# SD_card.net
KiCad netlist of a schematic drawn in Altium Designer
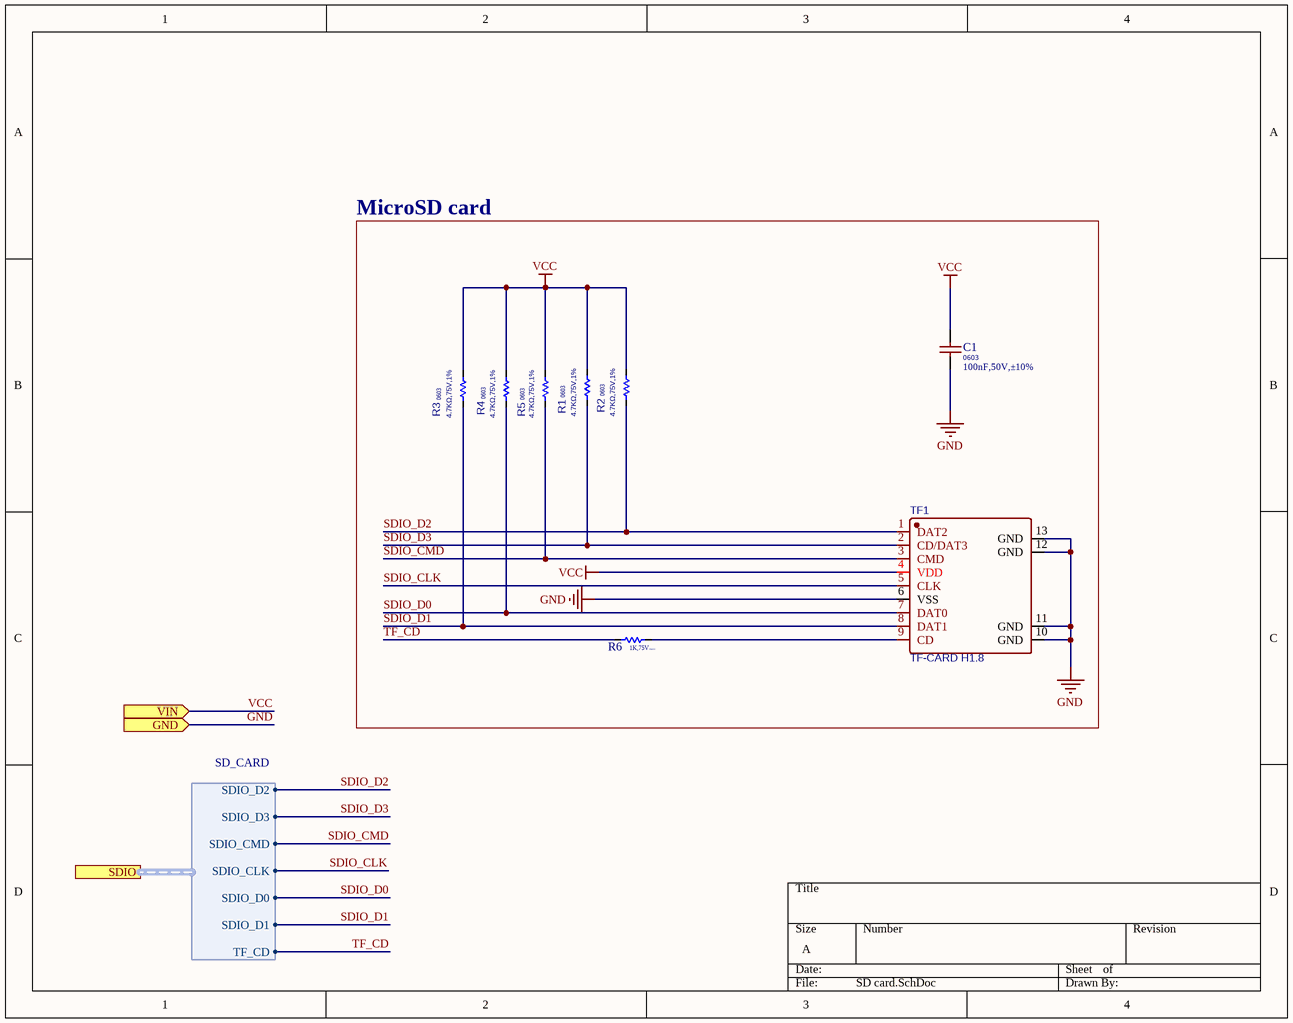
[diagram p0: SD card.SchDoc]

(export (version "E")
  (design (tool "Eeschema 10.0.6"))
  (components
    (comp (ref "C1")
      (value "100nF,50V,±10%")
      (footprint "RCL:C0603")
      (description "50V 100nF X7R ±10% 0603 Multilayer Ceramic Capacitors MLCC - SMD/SMT ROHS")
      (fields
        (field (name "MPN") "CL10B104KB8NNNC")
        (field (name "MANUFACTURER") "SAMSUNG")
        (field (name "PACKAGE") "0603")
      )
      (libsource (lib "RCL") (part "CL10B104KB8NNNC"))
    )
    (comp (ref "R1")
      (value "4.7KΩ,75V,1%")
      (footprint "R0603")
      (description "100mW Thick Film Resistors 75V ±100ppm/℃ ±1% 4.7kΩ 0603 Chip Resistor - Surface Mount ROHS")
      (fields
        (field (name "MANUFACTURER") "YAGEO")
        (field (name "MPN") "RC0603FR-071KL")
        (field (name "PACKAGE") "0603")
      )
      (libsource (lib "RCL") (part "RC0603FR-074K7L"))
    )
    (comp (ref "R2")
      (value "4.7KΩ,75V,1%")
      (footprint "R0603")
      (description "100mW Thick Film Resistors 75V ±100ppm/℃ ±1% 4.7kΩ 0603 Chip Resistor - Surface Mount ROHS")
      (fields
        (field (name "MANUFACTURER") "YAGEO")
        (field (name "MPN") "RC0603FR-071KL")
        (field (name "PACKAGE") "0603")
      )
      (libsource (lib "RCL") (part "RC0603FR-074K7L"))
    )
    (comp (ref "R3")
      (value "4.7KΩ,75V,1%")
      (footprint "R0603")
      (description "100mW Thick Film Resistors 75V ±100ppm/℃ ±1% 4.7kΩ 0603 Chip Resistor - Surface Mount ROHS")
      (fields
        (field (name "MANUFACTURER") "YAGEO")
        (field (name "MPN") "RC0603FR-071KL")
        (field (name "PACKAGE") "0603")
      )
      (libsource (lib "RCL") (part "RC0603FR-074K7L"))
    )
    (comp (ref "R4")
      (value "4.7KΩ,75V,1%")
      (footprint "R0603")
      (description "100mW Thick Film Resistors 75V ±100ppm/℃ ±1% 4.7kΩ 0603 Chip Resistor - Surface Mount ROHS")
      (fields
        (field (name "MANUFACTURER") "YAGEO")
        (field (name "MPN") "RC0603FR-071KL")
        (field (name "PACKAGE") "0603")
      )
      (libsource (lib "RCL") (part "RC0603FR-074K7L"))
    )
    (comp (ref "R5")
      (value "4.7KΩ,75V,1%")
      (footprint "R0603")
      (description "100mW Thick Film Resistors 75V ±100ppm/℃ ±1% 4.7kΩ 0603 Chip Resistor - Surface Mount ROHS")
      (fields
        (field (name "MANUFACTURER") "YAGEO")
        (field (name "MPN") "RC0603FR-071KL")
        (field (name "PACKAGE") "0603")
      )
      (libsource (lib "RCL") (part "RC0603FR-074K7L"))
    )
    (comp (ref "R6")
      (value "1K,75V")
      (footprint "R0603")
      (description "100mW Thick Film Resistors 75V ±100ppm/℃ ±1% 1kΩ 0603 Chip Resistor - Surface Mount ROHS")
      (fields
        (field (name "MANUFACTURER") "UNI-ROYAL(Uniroyal Elec)")
        (field (name "MPN") "0603WAF1001T5E")
        (field (name "PACKAGE") "0603")
      )
      (libsource (lib "RCL") (part "0603WAF1001T5E"))
    )
    (comp (ref "TF1")
      (value "TF-CARD H1.8")
      (footprint "sd card connector")
      (fields (field (name "MANUFACTURER") "SHOU HAN"))
      (libsource (lib "connector_button") (part "TF-CARD H1.8"))
    )
  )
  (nets
    (net (code "2") (name "/SDIO_CLK") (class "Default")
      (node (ref "TF1") (pin "5") (pinfunction "CLK_5") (pintype "passive"))
    )
    (net (code "3") (name "/SDIO_CMD") (class "Default")
      (node (ref "R5") (pin "1") (pinfunction "1_1") (pintype "passive"))
      (node (ref "TF1") (pin "3") (pinfunction "CMD_3") (pintype "passive"))
    )
    (net (code "4") (name "/SDIO_D0") (class "Default")
      (node (ref "R4") (pin "1") (pinfunction "1_1") (pintype "passive"))
      (node (ref "TF1") (pin "7") (pinfunction "DAT0_7") (pintype "passive"))
    )
    (net (code "5") (name "/SDIO_D1") (class "Default")
      (node (ref "R3") (pin "1") (pinfunction "1_1") (pintype "passive"))
      (node (ref "TF1") (pin "8") (pinfunction "DAT1_8") (pintype "passive"))
    )
    (net (code "6") (name "/SDIO_D2") (class "Default")
      (node (ref "R2") (pin "1") (pinfunction "1_1") (pintype "passive"))
      (node (ref "TF1") (pin "1") (pinfunction "DAT2_1") (pintype "passive"))
    )
    (net (code "7") (name "/SDIO_D3") (class "Default")
      (node (ref "R1") (pin "1") (pinfunction "1_1") (pintype "passive"))
      (node (ref "TF1") (pin "2") (pinfunction "CD/DAT3_2") (pintype "passive"))
    )
    (net (code "8") (name "/TF_CD") (class "Default")
      (node (ref "R6") (pin "1") (pinfunction "1_1") (pintype "passive"))
    )
    (net (code "10") (name "GND") (class "Default")
      (node (ref "C1") (pin "1") (pinfunction "1_1") (pintype "passive"))
      (node (ref "TF1") (pin "10") (pinfunction "GND_10") (pintype "passive"))
      (node (ref "TF1") (pin "11") (pinfunction "GND_11") (pintype "passive"))
      (node (ref "TF1") (pin "12") (pinfunction "GND_12") (pintype "passive"))
      (node (ref "TF1") (pin "13") (pinfunction "GND_13") (pintype "passive"))
      (node (ref "TF1") (pin "6") (pinfunction "VSS_6") (pintype "passive"))
    )
    (net (code "11") (name "Net-(TF1-CD)") (class "Default")
      (node (ref "R6") (pin "2") (pinfunction "2_2") (pintype "passive"))
      (node (ref "TF1") (pin "9") (pinfunction "CD_9") (pintype "passive"))
    )
    (net (code "12") (name "VCC") (class "Default")
      (node (ref "C1") (pin "2") (pinfunction "2_2") (pintype "passive"))
      (node (ref "R1") (pin "2") (pinfunction "2_2") (pintype "passive"))
      (node (ref "R2") (pin "2") (pinfunction "2_2") (pintype "passive"))
      (node (ref "R3") (pin "2") (pinfunction "2_2") (pintype "passive"))
      (node (ref "R4") (pin "2") (pinfunction "2_2") (pintype "passive"))
      (node (ref "R5") (pin "2") (pinfunction "2_2") (pintype "passive"))
      (node (ref "TF1") (pin "4") (pinfunction "VDD_4") (pintype "passive"))
    )
  )
)
